# BaoFengTRRSAdapter.net
KiCad netlist of a schematic drawn in EAGLE
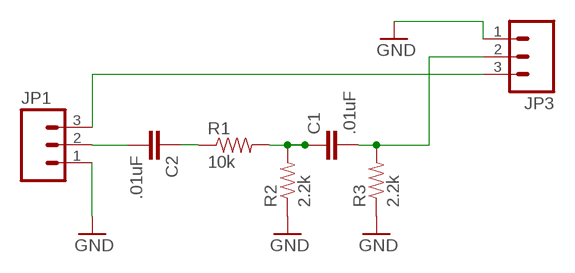
[diagram p0: schematic, sheet 1]

(export (version "E")
  (design (tool "Eeschema 10.0.6"))
  (components
    (comp (ref "C1")
      (value ".01uF")
      (footprint "eagle-import:0603-CAP")
      (libsource (lib "eagle-import") (part "CAP0603-CAP"))
    )
    (comp (ref "C2")
      (value ".01uF")
      (footprint "eagle-import:0603-CAP")
      (libsource (lib "eagle-import") (part "CAP0603-CAP"))
    )
    (comp (ref "JP1")
      (value "M031X03_NO_SILK")
      (footprint "eagle-import:1X03_NO_SILK")
      (libsource (lib "eagle-import") (part "M031X03_NO_SILK"))
    )
    (comp (ref "JP3")
      (value "M031X03_NO_SILK")
      (footprint "eagle-import:1X03_NO_SILK")
      (libsource (lib "eagle-import") (part "M031X03_NO_SILK"))
    )
    (comp (ref "R1")
      (value "10k")
      (footprint "eagle-import:0603-RES")
      (libsource (lib "eagle-import") (part "RESISTOR0603-RES"))
    )
    (comp (ref "R2")
      (value "2.2k")
      (footprint "eagle-import:0603-RES")
      (libsource (lib "eagle-import") (part "RESISTOR0603-RES"))
    )
    (comp (ref "R3")
      (value "2.2k")
      (footprint "eagle-import:0603-RES")
      (libsource (lib "eagle-import") (part "RESISTOR0603-RES"))
    )
  )
  (nets
    (net (code "1") (name "GND") (class "Default")
      (node (ref "JP1") (pin "1") (pinfunction "1_1") (pintype "passive"))
      (node (ref "JP3") (pin "1") (pinfunction "1_1") (pintype "passive"))
      (node (ref "R2") (pin "1") (pinfunction "1_1") (pintype "passive"))
      (node (ref "R3") (pin "1") (pinfunction "1_1") (pintype "passive"))
    )
    (net (code "2") (name "Net-(C1-Pad1)") (class "Default")
      (node (ref "C1") (pin "1") (pinfunction "1_1") (pintype "passive"))
      (node (ref "R1") (pin "2") (pinfunction "2_2") (pintype "passive"))
      (node (ref "R2") (pin "2") (pinfunction "2_2") (pintype "passive"))
    )
    (net (code "3") (name "Net-(C1-Pad2)") (class "Default")
      (node (ref "C1") (pin "2") (pinfunction "2_2") (pintype "passive"))
      (node (ref "JP3") (pin "2") (pinfunction "2_2") (pintype "passive"))
      (node (ref "R3") (pin "2") (pinfunction "2_2") (pintype "passive"))
    )
    (net (code "4") (name "Net-(C2-Pad1)") (class "Default")
      (node (ref "C2") (pin "1") (pinfunction "1_1") (pintype "passive"))
      (node (ref "R1") (pin "1") (pinfunction "1_1") (pintype "passive"))
    )
    (net (code "5") (name "Net-(C2-Pad2)") (class "Default")
      (node (ref "C2") (pin "2") (pinfunction "2_2") (pintype "passive"))
      (node (ref "JP1") (pin "2") (pinfunction "2_2") (pintype "passive"))
    )
    (net (code "6") (name "Net-(JP1-Pad3)") (class "Default")
      (node (ref "JP1") (pin "3") (pinfunction "3_3") (pintype "passive"))
      (node (ref "JP3") (pin "3") (pinfunction "3_3") (pintype "passive"))
    )
  )
)
